# Order_100038794_2Layer_Green_1_6mm_HASL_.net
KiCad netlist of a schematic drawn in EAGLE
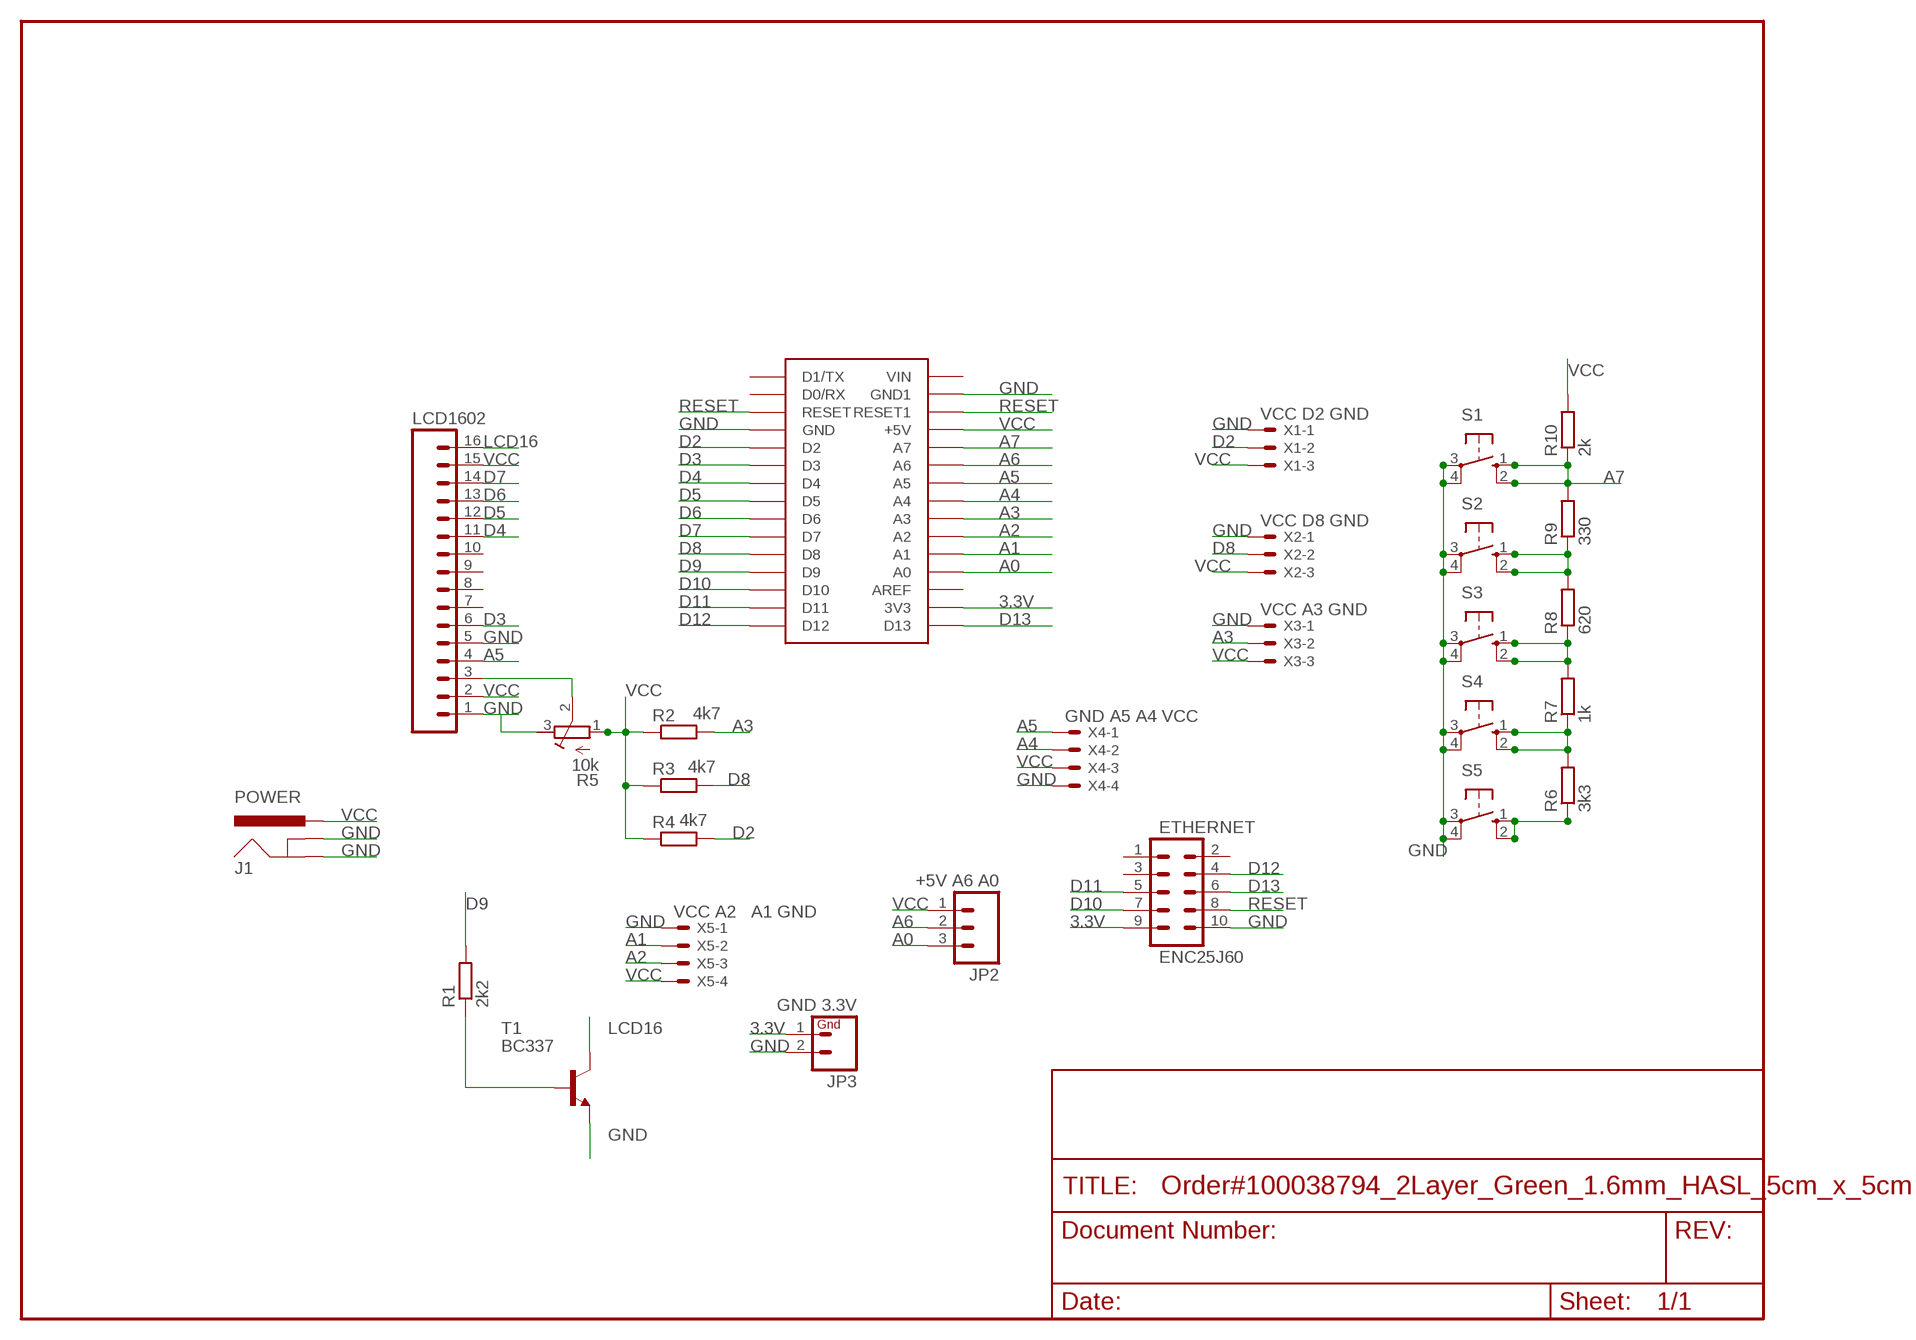
[diagram p0: schematic, sheet 1]

(export (version "E")
  (design (tool "Eeschema 10.0.6"))
  (components
    (comp (ref "ETHERNET")
      (value "ENC25J60")
      (footprint "eagle-import:AVR_ICSP")
      (libsource (lib "eagle-import") (part "M05X2PTH"))
    )
    (comp (ref "J1")
      (value "POWER")
      (footprint "eagle-import:POWER_JACK_PTH_LOCK")
      (libsource (lib "eagle-import") (part "POWER_JACKPTH_LOCK"))
    )
    (comp (ref "JP2")
      (value "+5V A6 A0")
      (footprint "eagle-import:1X03")
      (libsource (lib "eagle-import") (part "M03PTH"))
    )
    (comp (ref "JP3")
      (value "GND 3.3V")
      (footprint "eagle-import:1X02")
      (libsource (lib "eagle-import") (part "M02PTH"))
    )
    (comp (ref "LCD1602")
      (value "HEADER-16P-2.54")
      (footprint "eagle-import:16P-2.54")
      (libsource (lib "eagle-import") (part "HEADER-16P-2.54"))
    )
    (comp (ref "R1")
      (value "2k2")
      (footprint "eagle-import:0207_10")
      (libsource (lib "eagle-import") (part "R-EU_0207/10"))
    )
    (comp (ref "R2")
      (value "4k7")
      (footprint "eagle-import:0207_10")
      (libsource (lib "eagle-import") (part "R-EU_0207/10"))
    )
    (comp (ref "R3")
      (value "4k7")
      (footprint "eagle-import:0207_10")
      (libsource (lib "eagle-import") (part "R-EU_0207/10"))
    )
    (comp (ref "R4")
      (value "4k7")
      (footprint "eagle-import:0207_10")
      (libsource (lib "eagle-import") (part "R-EU_0207/10"))
    )
    (comp (ref "R5")
      (value "10k")
      (footprint "eagle-import:RTRIM64W")
      (libsource (lib "eagle-import") (part "R-TRIMM64W"))
    )
    (comp (ref "R6")
      (value "3k3")
      (footprint "eagle-import:0207_10")
      (libsource (lib "eagle-import") (part "R-EU_0207/10"))
    )
    (comp (ref "R7")
      (value "1k")
      (footprint "eagle-import:0207_10")
      (libsource (lib "eagle-import") (part "R-EU_0207/10"))
    )
    (comp (ref "R8")
      (value "620")
      (footprint "eagle-import:0207_10")
      (libsource (lib "eagle-import") (part "R-EU_0207/10"))
    )
    (comp (ref "R9")
      (value "330")
      (footprint "eagle-import:0207_10")
      (libsource (lib "eagle-import") (part "R-EU_0207/10"))
    )
    (comp (ref "R10")
      (value "2k")
      (footprint "eagle-import:0207_10")
      (libsource (lib "eagle-import") (part "R-EU_0207/10"))
    )
    (comp (ref "S1")
      (value "10-XX")
      (footprint "eagle-import:B3F-10XX")
      (fields (field (name "MPN") "B3F-1000"))
      (libsource (lib "eagle-import") (part "10-XX"))
    )
    (comp (ref "S2")
      (value "10-XX")
      (footprint "eagle-import:B3F-10XX")
      (fields (field (name "MPN") "B3F-1000"))
      (libsource (lib "eagle-import") (part "10-XX"))
    )
    (comp (ref "S3")
      (value "10-XX")
      (footprint "eagle-import:B3F-10XX")
      (fields (field (name "MPN") "B3F-1000"))
      (libsource (lib "eagle-import") (part "10-XX"))
    )
    (comp (ref "S4")
      (value "10-XX")
      (footprint "eagle-import:B3F-10XX")
      (fields (field (name "MPN") "B3F-1000"))
      (libsource (lib "eagle-import") (part "10-XX"))
    )
    (comp (ref "S5")
      (value "10-XX")
      (footprint "eagle-import:B3F-10XX")
      (fields (field (name "MPN") "B3F-1000"))
      (libsource (lib "eagle-import") (part "10-XX"))
    )
    (comp (ref "T1")
      (value "BC337")
      (footprint "eagle-import:TO92")
      (libsource (lib "eagle-import") (part "BC337"))
    )
    (comp (ref "U$2")
      (value "ARDUINONANO")
      (footprint "eagle-import:PDIP-32")
      (libsource (lib "eagle-import") (part "ARDUINONANO"))
    )
    (comp (ref "X1")
      (value "VCC D2 GND")
      (footprint "eagle-import:22-23-2031")
      (fields (field (name "MF") "MOLEX") (field (name "MPN") "22-23-2031"))
      (libsource (lib "eagle-import") (part "22-23-2031"))
    )
    (comp (ref "X2")
      (value "VCC D8 GND")
      (footprint "eagle-import:22-23-2031")
      (fields (field (name "MF") "MOLEX") (field (name "MPN") "22-23-2031"))
      (libsource (lib "eagle-import") (part "22-23-2031"))
    )
    (comp (ref "X3")
      (value "VCC A3 GND")
      (footprint "eagle-import:22-23-2031")
      (fields (field (name "MF") "MOLEX") (field (name "MPN") "22-23-2031"))
      (libsource (lib "eagle-import") (part "22-23-2031"))
    )
    (comp (ref "X4")
      (value "GND A5 A4 VCC")
      (footprint "eagle-import:22-23-2041")
      (fields (field (name "MF") "MOLEX") (field (name "MPN") "22-23-2041"))
      (libsource (lib "eagle-import") (part "22-23-2041"))
    )
    (comp (ref "X5")
      (value "VCC A2 A1 GND")
      (footprint "eagle-import:22-23-2041")
      (fields (field (name "MF") "MOLEX") (field (name "MPN") "22-23-2041"))
      (libsource (lib "eagle-import") (part "22-23-2041"))
    )
  )
  (nets
    (net (code "1") (name "/3.3V") (class "Default")
      (node (ref "ETHERNET") (pin "9") (pinfunction "9_9") (pintype "passive"))
      (node (ref "JP3") (pin "1") (pinfunction "1_1") (pintype "passive"))
      (node (ref "U$2") (pin "3V3") (pinfunction "3V3_3V3") (pintype "bidirectional"))
    )
    (net (code "2") (name "/A0") (class "Default")
      (node (ref "JP2") (pin "3") (pinfunction "3_3") (pintype "passive"))
      (node (ref "U$2") (pin "A0") (pinfunction "A0_A0") (pintype "bidirectional"))
    )
    (net (code "3") (name "/A1") (class "Default")
      (node (ref "U$2") (pin "A1") (pinfunction "A1_A1") (pintype "bidirectional"))
      (node (ref "X5") (pin "2") (pinfunction "S_2") (pintype "passive"))
    )
    (net (code "4") (name "/A2") (class "Default")
      (node (ref "U$2") (pin "A2") (pinfunction "A2_A2") (pintype "bidirectional"))
      (node (ref "X5") (pin "3") (pinfunction "S_3") (pintype "passive"))
    )
    (net (code "5") (name "/A3") (class "Default")
      (node (ref "R2") (pin "2") (pinfunction "2_2") (pintype "passive"))
      (node (ref "U$2") (pin "A3") (pinfunction "A3_A3") (pintype "bidirectional"))
      (node (ref "X3") (pin "2") (pinfunction "S_2") (pintype "passive"))
    )
    (net (code "6") (name "/A4") (class "Default")
      (node (ref "U$2") (pin "A4") (pinfunction "A4_A4") (pintype "bidirectional"))
      (node (ref "X4") (pin "2") (pinfunction "S_2") (pintype "passive"))
    )
    (net (code "7") (name "/A5") (class "Default")
      (node (ref "LCD1602") (pin "4") (pinfunction "4_4") (pintype "passive"))
      (node (ref "U$2") (pin "A5") (pinfunction "A5_A5") (pintype "bidirectional"))
      (node (ref "X4") (pin "1") (pinfunction "S_1") (pintype "passive"))
    )
    (net (code "8") (name "/A6") (class "Default")
      (node (ref "JP2") (pin "2") (pinfunction "2_2") (pintype "passive"))
      (node (ref "U$2") (pin "A6") (pinfunction "A6_A6") (pintype "bidirectional"))
    )
    (net (code "9") (name "/A7") (class "Default")
      (node (ref "R10") (pin "1") (pinfunction "1_1") (pintype "passive"))
      (node (ref "R9") (pin "2") (pinfunction "2_2") (pintype "passive"))
      (node (ref "S1") (pin "1") (pinfunction "S_1") (pintype "passive"))
      (node (ref "S1") (pin "2") (pinfunction "S1_2") (pintype "passive"))
      (node (ref "U$2") (pin "A7") (pinfunction "A7_A7") (pintype "bidirectional"))
    )
    (net (code "10") (name "/D2") (class "Default")
      (node (ref "R4") (pin "2") (pinfunction "2_2") (pintype "passive"))
      (node (ref "U$2") (pin "D2") (pinfunction "D2_D2") (pintype "bidirectional"))
      (node (ref "X1") (pin "2") (pinfunction "S_2") (pintype "passive"))
    )
    (net (code "11") (name "/D3") (class "Default")
      (node (ref "LCD1602") (pin "6") (pinfunction "6_6") (pintype "passive"))
      (node (ref "U$2") (pin "D3") (pinfunction "D3_D3") (pintype "bidirectional"))
    )
    (net (code "12") (name "/D4") (class "Default")
      (node (ref "LCD1602") (pin "11") (pinfunction "11_11") (pintype "passive"))
      (node (ref "U$2") (pin "D4") (pinfunction "D4_D4") (pintype "bidirectional"))
    )
    (net (code "13") (name "/D5") (class "Default")
      (node (ref "LCD1602") (pin "12") (pinfunction "12_12") (pintype "passive"))
      (node (ref "U$2") (pin "D5") (pinfunction "D5_D5") (pintype "bidirectional"))
    )
    (net (code "14") (name "/D6") (class "Default")
      (node (ref "LCD1602") (pin "13") (pinfunction "13_13") (pintype "passive"))
      (node (ref "U$2") (pin "D6") (pinfunction "D6_D6") (pintype "bidirectional"))
    )
    (net (code "15") (name "/D7") (class "Default")
      (node (ref "LCD1602") (pin "14") (pinfunction "14_14") (pintype "passive"))
      (node (ref "U$2") (pin "D7") (pinfunction "D7_D7") (pintype "bidirectional"))
    )
    (net (code "16") (name "/D8") (class "Default")
      (node (ref "R3") (pin "2") (pinfunction "2_2") (pintype "passive"))
      (node (ref "U$2") (pin "D8") (pinfunction "D8_D8") (pintype "bidirectional"))
      (node (ref "X2") (pin "2") (pinfunction "S_2") (pintype "passive"))
    )
    (net (code "17") (name "/D9") (class "Default")
      (node (ref "R1") (pin "2") (pinfunction "2_2") (pintype "passive"))
      (node (ref "U$2") (pin "D9") (pinfunction "D9_D9") (pintype "bidirectional"))
    )
    (net (code "18") (name "/D10") (class "Default")
      (node (ref "ETHERNET") (pin "7") (pinfunction "7_7") (pintype "passive"))
      (node (ref "U$2") (pin "D10") (pinfunction "D10_D10") (pintype "bidirectional"))
    )
    (net (code "19") (name "/D11") (class "Default")
      (node (ref "ETHERNET") (pin "5") (pinfunction "5_5") (pintype "passive"))
      (node (ref "U$2") (pin "D11") (pinfunction "D11_D11") (pintype "bidirectional"))
    )
    (net (code "20") (name "/D12") (class "Default")
      (node (ref "ETHERNET") (pin "4") (pinfunction "4_4") (pintype "passive"))
      (node (ref "U$2") (pin "D12") (pinfunction "D12_D12") (pintype "bidirectional"))
    )
    (net (code "21") (name "/D13") (class "Default")
      (node (ref "ETHERNET") (pin "6") (pinfunction "6_6") (pintype "passive"))
      (node (ref "U$2") (pin "D13") (pinfunction "D13_D13") (pintype "bidirectional"))
    )
    (net (code "22") (name "/GND") (class "Default")
      (node (ref "ETHERNET") (pin "10") (pinfunction "10_10") (pintype "passive"))
      (node (ref "J1") (pin "GND") (pinfunction "GND_GND") (pintype "bidirectional"))
      (node (ref "J1") (pin "GNDBREAK") (pinfunction "GNDBREAK_GNDBREAK") (pintype "bidirectional"))
      (node (ref "JP3") (pin "2") (pinfunction "2_2") (pintype "passive"))
      (node (ref "LCD1602") (pin "1") (pinfunction "1_1") (pintype "passive"))
      (node (ref "LCD1602") (pin "5") (pinfunction "5_5") (pintype "passive"))
      (node (ref "R5") (pin "3") (pinfunction "A_3") (pintype "passive"))
      (node (ref "S1") (pin "3") (pinfunction "P_3") (pintype "passive"))
      (node (ref "S1") (pin "4") (pinfunction "P1_4") (pintype "passive"))
      (node (ref "S2") (pin "3") (pinfunction "P_3") (pintype "passive"))
      (node (ref "S2") (pin "4") (pinfunction "P1_4") (pintype "passive"))
      (node (ref "S3") (pin "3") (pinfunction "P_3") (pintype "passive"))
      (node (ref "S3") (pin "4") (pinfunction "P1_4") (pintype "passive"))
      (node (ref "S4") (pin "3") (pinfunction "P_3") (pintype "passive"))
      (node (ref "S4") (pin "4") (pinfunction "P1_4") (pintype "passive"))
      (node (ref "S5") (pin "3") (pinfunction "P_3") (pintype "passive"))
      (node (ref "S5") (pin "4") (pinfunction "P1_4") (pintype "passive"))
      (node (ref "T1") (pin "1") (pinfunction "E_1") (pintype "passive"))
      (node (ref "U$2") (pin "GND") (pinfunction "GND_GND") (pintype "bidirectional"))
      (node (ref "U$2") (pin "GND1") (pinfunction "GND1_GND1") (pintype "bidirectional"))
      (node (ref "X1") (pin "1") (pinfunction "S_1") (pintype "passive"))
      (node (ref "X2") (pin "1") (pinfunction "S_1") (pintype "passive"))
      (node (ref "X3") (pin "1") (pinfunction "S_1") (pintype "passive"))
      (node (ref "X4") (pin "4") (pinfunction "S_4") (pintype "passive"))
      (node (ref "X5") (pin "1") (pinfunction "S_1") (pintype "passive"))
    )
    (net (code "23") (name "/LCD16") (class "Default")
      (node (ref "LCD1602") (pin "16") (pinfunction "16_16") (pintype "passive"))
      (node (ref "T1") (pin "3") (pinfunction "C_3") (pintype "passive"))
    )
    (net (code "24") (name "/RESET") (class "Default")
      (node (ref "ETHERNET") (pin "8") (pinfunction "8_8") (pintype "passive"))
      (node (ref "U$2") (pin "RESET") (pinfunction "RESET_RESET") (pintype "bidirectional"))
      (node (ref "U$2") (pin "RESET1") (pinfunction "RESET1_RESET1") (pintype "bidirectional"))
    )
    (net (code "25") (name "/VCC") (class "Default")
      (node (ref "J1") (pin "PWR") (pinfunction "PWR_PWR") (pintype "bidirectional"))
      (node (ref "JP2") (pin "1") (pinfunction "1_1") (pintype "passive"))
      (node (ref "LCD1602") (pin "15") (pinfunction "15_15") (pintype "passive"))
      (node (ref "LCD1602") (pin "2") (pinfunction "2_2") (pintype "passive"))
      (node (ref "R10") (pin "2") (pinfunction "2_2") (pintype "passive"))
      (node (ref "R2") (pin "1") (pinfunction "1_1") (pintype "passive"))
      (node (ref "R3") (pin "1") (pinfunction "1_1") (pintype "passive"))
      (node (ref "R4") (pin "1") (pinfunction "1_1") (pintype "passive"))
      (node (ref "R5") (pin "1") (pinfunction "E_1") (pintype "passive"))
      (node (ref "U$2") (pin "+5V") (pinfunction "+5V_+5V") (pintype "bidirectional"))
      (node (ref "X1") (pin "3") (pinfunction "S_3") (pintype "passive"))
      (node (ref "X2") (pin "3") (pinfunction "S_3") (pintype "passive"))
      (node (ref "X3") (pin "3") (pinfunction "S_3") (pintype "passive"))
      (node (ref "X4") (pin "3") (pinfunction "S_3") (pintype "passive"))
      (node (ref "X5") (pin "4") (pinfunction "S_4") (pintype "passive"))
    )
    (net (code "26") (name "Net-(R5-S)") (class "Default")
      (node (ref "LCD1602") (pin "3") (pinfunction "3_3") (pintype "passive"))
      (node (ref "R5") (pin "2") (pinfunction "S_2") (pintype "passive"))
    )
    (net (code "27") (name "Net-(S2-S)") (class "Default")
      (node (ref "R8") (pin "2") (pinfunction "2_2") (pintype "passive"))
      (node (ref "R9") (pin "1") (pinfunction "1_1") (pintype "passive"))
      (node (ref "S2") (pin "1") (pinfunction "S_1") (pintype "passive"))
      (node (ref "S2") (pin "2") (pinfunction "S1_2") (pintype "passive"))
    )
    (net (code "28") (name "Net-(S3-S)") (class "Default")
      (node (ref "R7") (pin "2") (pinfunction "2_2") (pintype "passive"))
      (node (ref "R8") (pin "1") (pinfunction "1_1") (pintype "passive"))
      (node (ref "S3") (pin "1") (pinfunction "S_1") (pintype "passive"))
      (node (ref "S3") (pin "2") (pinfunction "S1_2") (pintype "passive"))
    )
    (net (code "29") (name "Net-(S4-S)") (class "Default")
      (node (ref "R6") (pin "2") (pinfunction "2_2") (pintype "passive"))
      (node (ref "R7") (pin "1") (pinfunction "1_1") (pintype "passive"))
      (node (ref "S4") (pin "1") (pinfunction "S_1") (pintype "passive"))
      (node (ref "S4") (pin "2") (pinfunction "S1_2") (pintype "passive"))
    )
    (net (code "30") (name "Net-(S5-S)") (class "Default")
      (node (ref "R6") (pin "1") (pinfunction "1_1") (pintype "passive"))
      (node (ref "S5") (pin "1") (pinfunction "S_1") (pintype "passive"))
      (node (ref "S5") (pin "2") (pinfunction "S1_2") (pintype "passive"))
    )
    (net (code "31") (name "Net-(T1-B)") (class "Default")
      (node (ref "R1") (pin "1") (pinfunction "1_1") (pintype "passive"))
      (node (ref "T1") (pin "2") (pinfunction "B_2") (pintype "passive"))
    )
    (net (code "32") (name "unconnected-(ETHERNET-Pad1)") (class "Default")
      (node (ref "ETHERNET") (pin "1") (pinfunction "1_1") (pintype "passive"))
    )
    (net (code "33") (name "unconnected-(ETHERNET-Pad2)") (class "Default")
      (node (ref "ETHERNET") (pin "2") (pinfunction "2_2") (pintype "passive"))
    )
    (net (code "34") (name "unconnected-(ETHERNET-Pad3)") (class "Default")
      (node (ref "ETHERNET") (pin "3") (pinfunction "3_3") (pintype "passive"))
    )
    (net (code "35") (name "unconnected-(LCD1602-Pad7)") (class "Default")
      (node (ref "LCD1602") (pin "7") (pinfunction "7_7") (pintype "passive"))
    )
    (net (code "36") (name "unconnected-(LCD1602-Pad8)") (class "Default")
      (node (ref "LCD1602") (pin "8") (pinfunction "8_8") (pintype "passive"))
    )
    (net (code "37") (name "unconnected-(LCD1602-Pad9)") (class "Default")
      (node (ref "LCD1602") (pin "9") (pinfunction "9_9") (pintype "passive"))
    )
    (net (code "38") (name "unconnected-(LCD1602-Pad10)") (class "Default")
      (node (ref "LCD1602") (pin "10") (pinfunction "10_10") (pintype "passive"))
    )
    (net (code "39") (name "unconnected-(U$2-PadAREF)") (class "Default")
      (node (ref "U$2") (pin "AREF") (pinfunction "AREF_AREF") (pintype "bidirectional"))
    )
    (net (code "40") (name "unconnected-(U$2-PadD0{slash}RX)") (class "Default")
      (node (ref "U$2") (pin "D0/RX") (pinfunction "D0/RX_D0/RX") (pintype "bidirectional"))
    )
    (net (code "41") (name "unconnected-(U$2-PadD1{slash}TX)") (class "Default")
      (node (ref "U$2") (pin "D1/TX") (pinfunction "D1/TX_D1/TX") (pintype "bidirectional"))
    )
    (net (code "42") (name "unconnected-(U$2-PadVIN)") (class "Default")
      (node (ref "U$2") (pin "VIN") (pinfunction "VIN_VIN") (pintype "bidirectional"))
    )
  )
)
